# mag_encoder.net
KiCad netlist of a schematic drawn in EAGLE
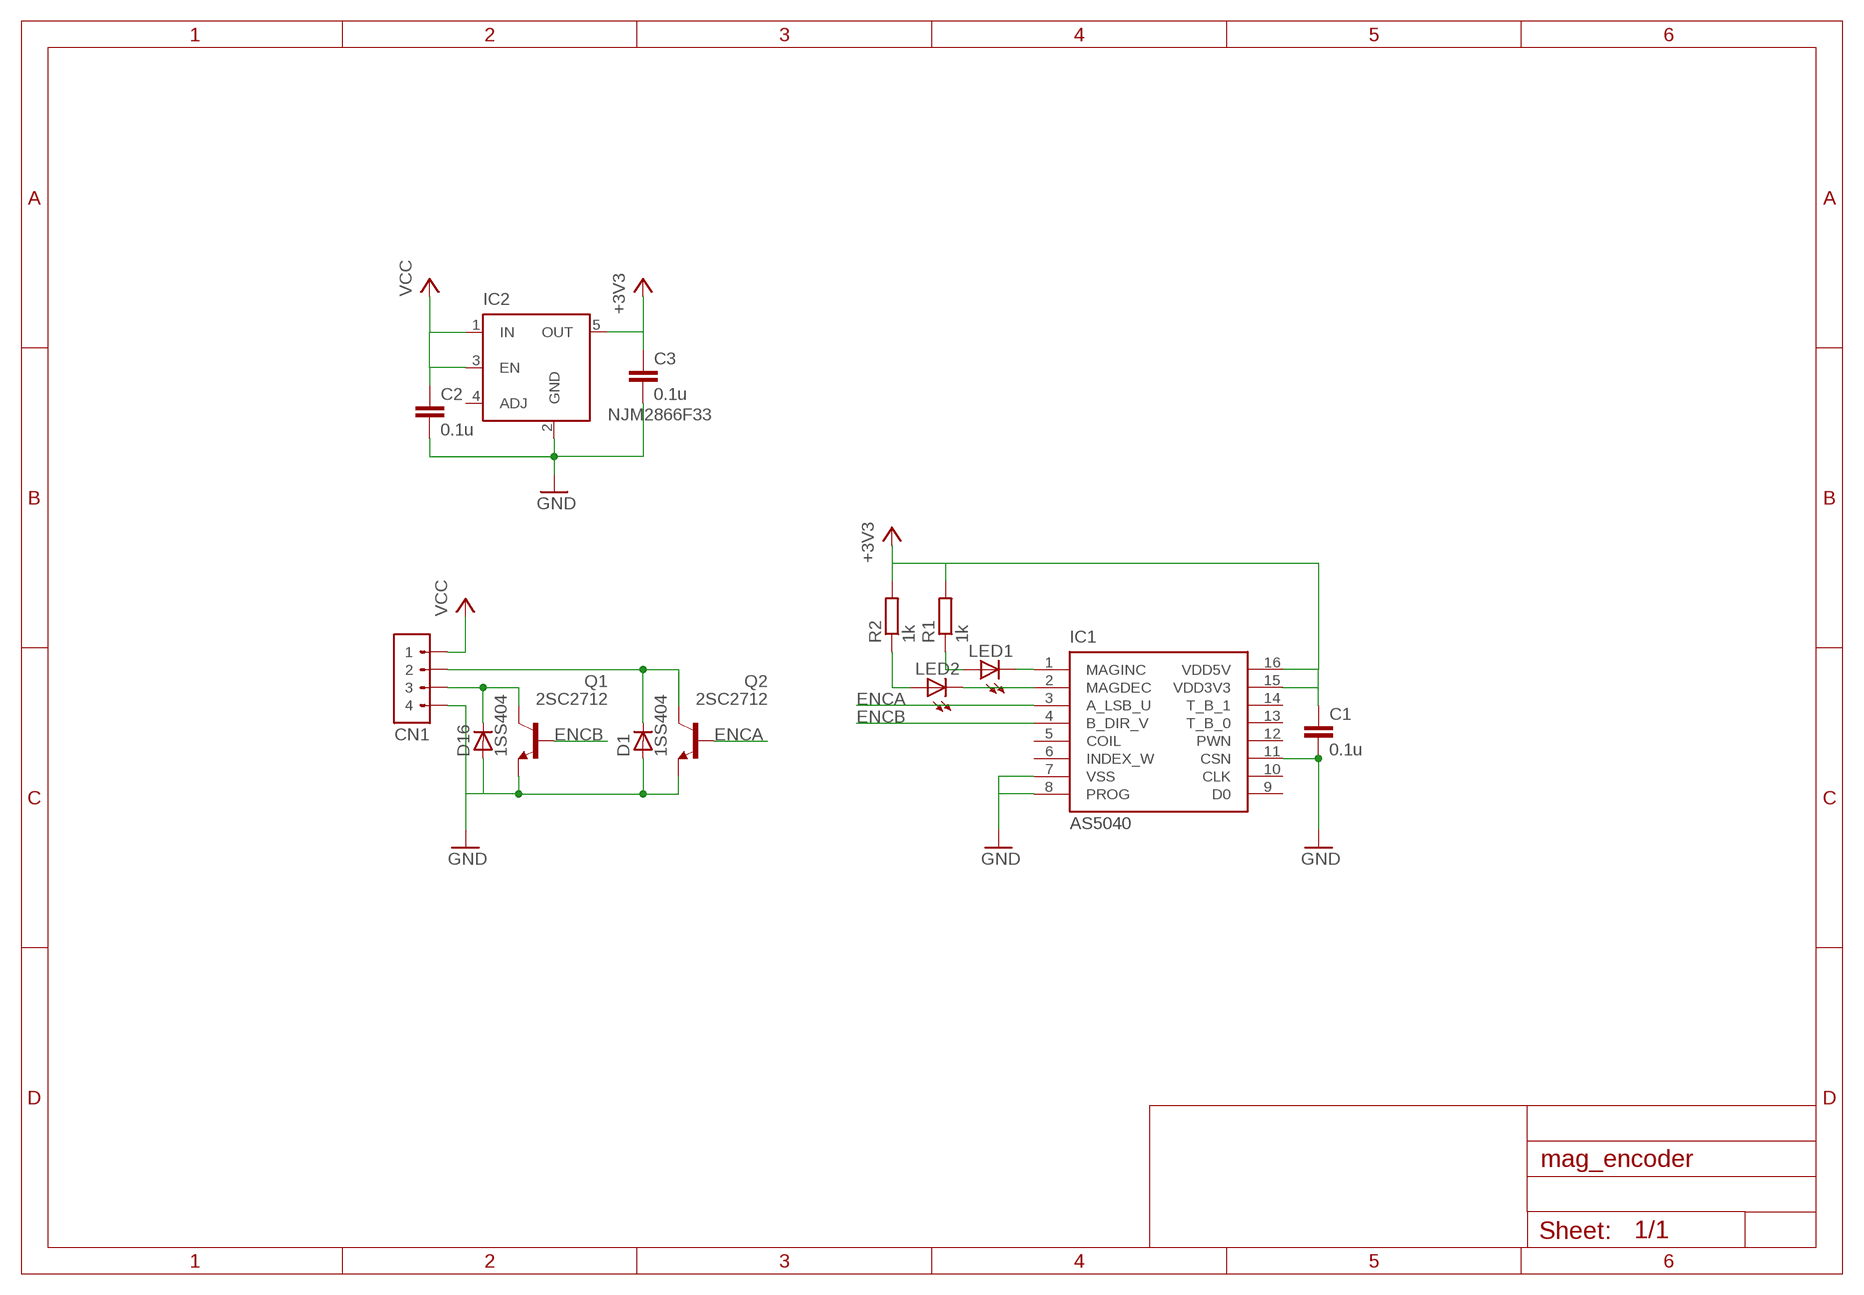
[diagram p0: schematic, sheet 1]

(export (version "E")
  (design (tool "Eeschema 10.0.6"))
  (components
    (comp (ref "C1")
      (value "0.1u")
      (footprint "eagle-import:C0603K")
      (libsource (lib "eagle-import") (part "C-EUC0603K"))
    )
    (comp (ref "C2")
      (value "0.1u")
      (footprint "eagle-import:C0603K")
      (libsource (lib "eagle-import") (part "C-EUC0603K"))
    )
    (comp (ref "C3")
      (value "0.1u")
      (footprint "eagle-import:C0603K")
      (libsource (lib "eagle-import") (part "C-EUC0603K"))
    )
    (comp (ref "CN1")
      (value "CN4-JST-XH-TOP")
      (footprint "eagle-import:JST-B4B-XH-A")
      (libsource (lib "eagle-import") (part "CN4-JST-XH-TOP"))
    )
    (comp (ref "D1")
      (value "1SS404")
      (footprint "eagle-import:USC(1.25X2.5)")
      (libsource (lib "eagle-import") (part "1SS404"))
    )
    (comp (ref "D16")
      (value "1SS404")
      (footprint "eagle-import:USC(1.25X2.5)")
      (libsource (lib "eagle-import") (part "1SS404"))
    )
    (comp (ref "IC1")
      (value "AS5040")
      (footprint "eagle-import:SSOP16")
      (libsource (lib "eagle-import") (part "AS5040"))
    )
    (comp (ref "IC2")
      (value "NJM2866F33")
      (footprint "eagle-import:SOT23-5")
      (fields (field (name "MF") "ALTERA CORPORATION") (field (name "MPN") "MIC5219BM5 TR"))
      (libsource (lib "eagle-import") (part "MIC5219BM5"))
    )
    (comp (ref "LED1")
      (value "LEDSML0603")
      (footprint "eagle-import:SML0603")
      (libsource (lib "eagle-import") (part "LEDSML0603"))
    )
    (comp (ref "LED2")
      (value "LEDSML0603")
      (footprint "eagle-import:SML0603")
      (libsource (lib "eagle-import") (part "LEDSML0603"))
    )
    (comp (ref "Q1")
      (value "2SC2712")
      (footprint "eagle-import:SC-59(TYPE1)")
      (libsource (lib "eagle-import") (part "2SC2712"))
    )
    (comp (ref "Q2")
      (value "2SC2712")
      (footprint "eagle-import:SC-59(TYPE1)")
      (libsource (lib "eagle-import") (part "2SC2712"))
    )
    (comp (ref "R1")
      (value "1k")
      (footprint "eagle-import:R0603")
      (libsource (lib "eagle-import") (part "R-EU_R0603"))
    )
    (comp (ref "R2")
      (value "1k")
      (footprint "eagle-import:R0603")
      (libsource (lib "eagle-import") (part "R-EU_R0603"))
    )
  )
  (nets
    (net (code "1") (name "+3V3") (class "Default")
      (node (ref "C1") (pin "1") (pinfunction "1_1") (pintype "passive"))
      (node (ref "C3") (pin "1") (pinfunction "1_1") (pintype "passive"))
      (node (ref "IC1") (pin "15") (pinfunction "VDD3V3_15") (pintype "passive"))
      (node (ref "IC1") (pin "16") (pinfunction "VDD5V_16") (pintype "passive"))
      (node (ref "IC2") (pin "5") (pinfunction "OUT_5") (pintype "output"))
      (node (ref "R1") (pin "2") (pinfunction "2_2") (pintype "passive"))
      (node (ref "R2") (pin "2") (pinfunction "2_2") (pintype "passive"))
    )
    (net (code "2") (name "/ENCA") (class "Default")
      (node (ref "IC1") (pin "3") (pinfunction "A_LSB_U_3") (pintype "output"))
      (node (ref "Q2") (pin "B") (pinfunction "B_B") (pintype "passive"))
    )
    (net (code "3") (name "/ENCB") (class "Default")
      (node (ref "IC1") (pin "4") (pinfunction "B_DIR_V_4") (pintype "output"))
      (node (ref "Q1") (pin "B") (pinfunction "B_B") (pintype "passive"))
    )
    (net (code "4") (name "GND") (class "Default")
      (node (ref "C1") (pin "2") (pinfunction "2_2") (pintype "passive"))
      (node (ref "C2") (pin "2") (pinfunction "2_2") (pintype "passive"))
      (node (ref "C3") (pin "2") (pinfunction "2_2") (pintype "passive"))
      (node (ref "CN1") (pin "4") (pinfunction "4_4") (pintype "passive"))
      (node (ref "D1") (pin "A") (pinfunction "A_A") (pintype "passive"))
      (node (ref "D16") (pin "A") (pinfunction "A_A") (pintype "passive"))
      (node (ref "IC1") (pin "11") (pinfunction "CSN_11") (pintype "input"))
      (node (ref "IC1") (pin "7") (pinfunction "VSS_7") (pintype "passive"))
      (node (ref "IC1") (pin "8") (pinfunction "PROG_8") (pintype "input"))
      (node (ref "IC2") (pin "2") (pinfunction "GND_2") (pintype "power_in"))
      (node (ref "Q1") (pin "E") (pinfunction "E_E") (pintype "passive"))
      (node (ref "Q2") (pin "E") (pinfunction "E_E") (pintype "passive"))
    )
    (net (code "5") (name "Net-(D1-C)") (class "Default")
      (node (ref "CN1") (pin "2") (pinfunction "2_2") (pintype "passive"))
      (node (ref "D1") (pin "K") (pinfunction "C_K") (pintype "passive"))
      (node (ref "Q2") (pin "C") (pinfunction "C_C") (pintype "passive"))
    )
    (net (code "6") (name "Net-(D16-C)") (class "Default")
      (node (ref "CN1") (pin "3") (pinfunction "3_3") (pintype "passive"))
      (node (ref "D16") (pin "K") (pinfunction "C_K") (pintype "passive"))
      (node (ref "Q1") (pin "C") (pinfunction "C_C") (pintype "passive"))
    )
    (net (code "7") (name "Net-(IC1-MAGDEC)") (class "Default")
      (node (ref "IC1") (pin "2") (pinfunction "MAGDEC_2") (pintype "tri_state"))
      (node (ref "LED2") (pin "C") (pinfunction "C_C") (pintype "passive"))
    )
    (net (code "8") (name "Net-(IC1-MAGINC)") (class "Default")
      (node (ref "IC1") (pin "1") (pinfunction "MAGINC_1") (pintype "tri_state"))
      (node (ref "LED1") (pin "C") (pinfunction "C_C") (pintype "passive"))
    )
    (net (code "9") (name "Net-(LED1-PadA)") (class "Default")
      (node (ref "LED1") (pin "A") (pinfunction "A_A") (pintype "passive"))
      (node (ref "R1") (pin "1") (pinfunction "1_1") (pintype "passive"))
    )
    (net (code "10") (name "Net-(LED2-PadA)") (class "Default")
      (node (ref "LED2") (pin "A") (pinfunction "A_A") (pintype "passive"))
      (node (ref "R2") (pin "1") (pinfunction "1_1") (pintype "passive"))
    )
    (net (code "11") (name "VCC") (class "Default")
      (node (ref "C2") (pin "1") (pinfunction "1_1") (pintype "passive"))
      (node (ref "CN1") (pin "1") (pinfunction "1_1") (pintype "passive"))
      (node (ref "IC2") (pin "1") (pinfunction "IN_1") (pintype "input"))
      (node (ref "IC2") (pin "3") (pinfunction "EN_3") (pintype "input"))
    )
    (net (code "12") (name "unconnected-(IC1-CLK-Pad10)") (class "Default")
      (node (ref "IC1") (pin "10") (pinfunction "CLK_10") (pintype "input"))
    )
    (net (code "13") (name "unconnected-(IC1-COIL-Pad5)") (class "Default")
      (node (ref "IC1") (pin "5") (pinfunction "COIL_5") (pintype "no_connect"))
    )
    (net (code "14") (name "unconnected-(IC1-D0-Pad9)") (class "Default")
      (node (ref "IC1") (pin "9") (pinfunction "D0_9") (pintype "tri_state"))
    )
    (net (code "15") (name "unconnected-(IC1-INDEX_W-Pad6)") (class "Default")
      (node (ref "IC1") (pin "6") (pinfunction "INDEX_W_6") (pintype "output"))
    )
    (net (code "16") (name "unconnected-(IC1-PWN-Pad12)") (class "Default")
      (node (ref "IC1") (pin "12") (pinfunction "PWN_12") (pintype "passive"))
    )
    (net (code "17") (name "unconnected-(IC1-T_B_0-Pad13)") (class "Default")
      (node (ref "IC1") (pin "13") (pinfunction "T_B_0_13") (pintype "no_connect"))
    )
    (net (code "18") (name "unconnected-(IC1-T_B_1-Pad14)") (class "Default")
      (node (ref "IC1") (pin "14") (pinfunction "T_B_1_14") (pintype "no_connect"))
    )
    (net (code "19") (name "unconnected-(IC2-ADJ-Pad4)") (class "Default")
      (node (ref "IC2") (pin "4") (pinfunction "ADJ_4") (pintype "passive"))
    )
  )
)
